# 1-Schematic_sfy1.net
KiCad netlist of a schematic drawn in EasyEDA
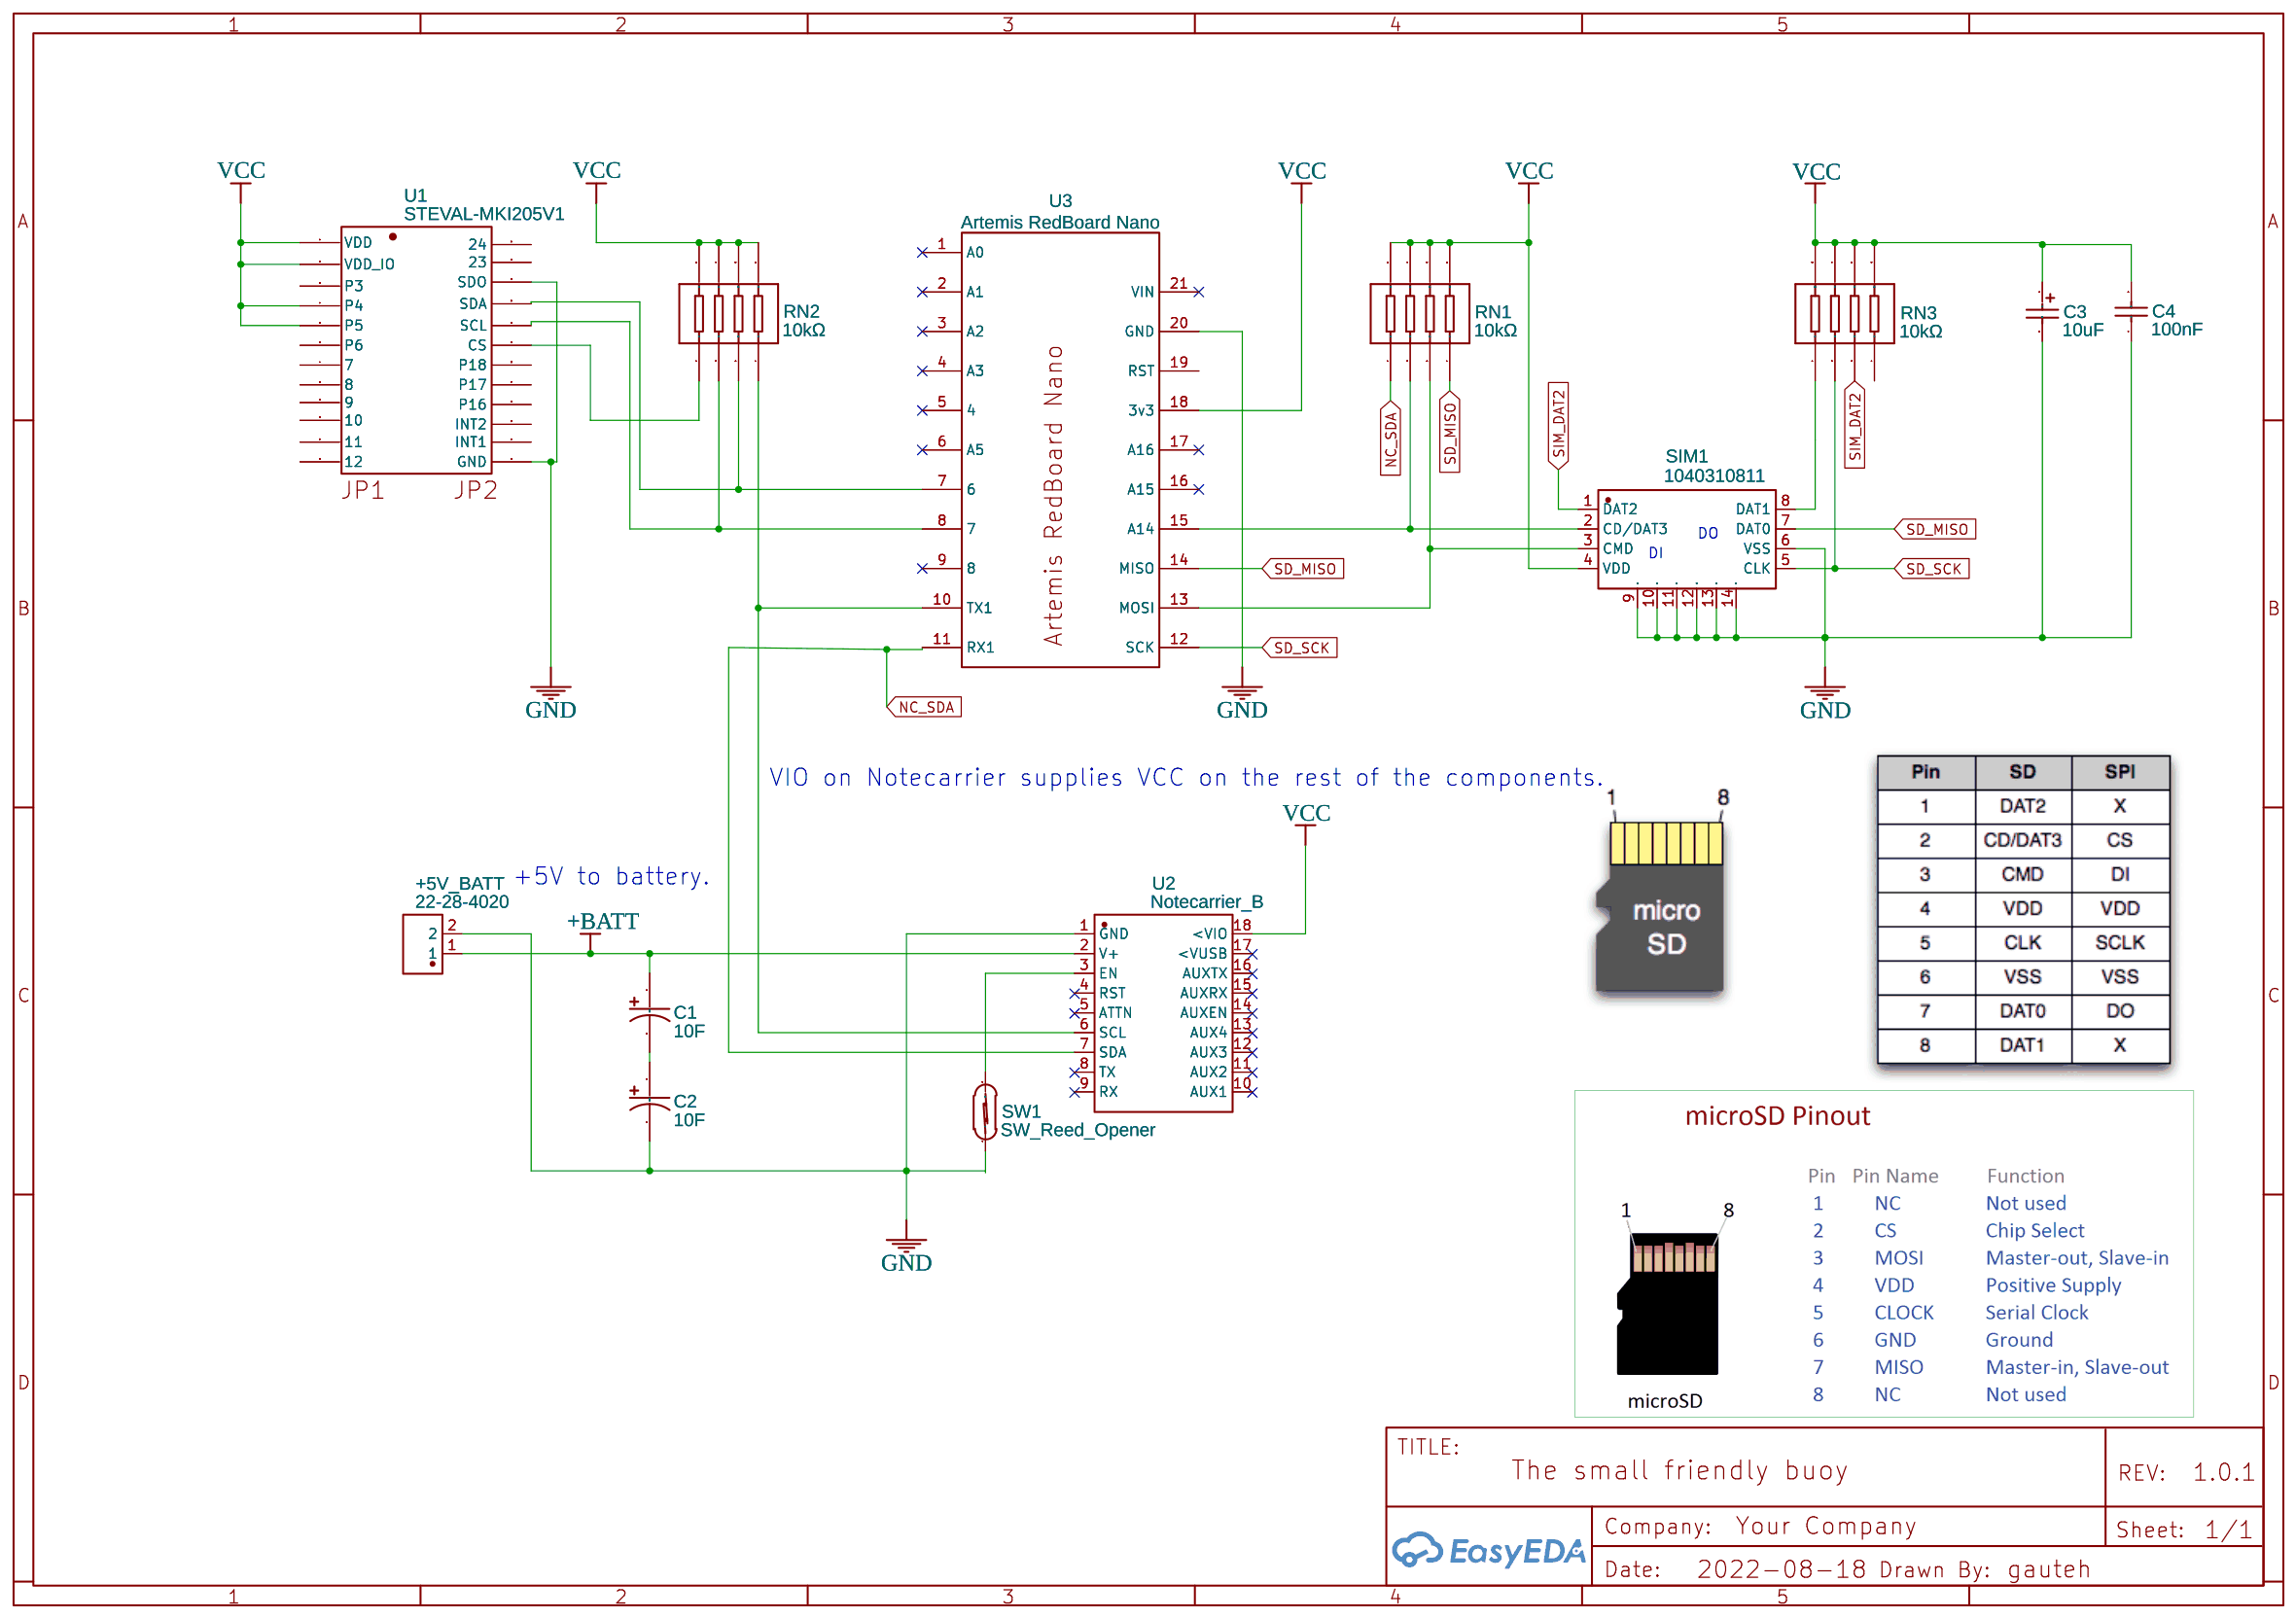
[diagram p0: schematic sheet]

(export (version "E")
  (design (tool "Eeschema 10.0.6"))
  (components
    (comp (ref "+5V_BATT")
      (value "22-28-4020")
      (fields (field (name "BOM_Supplier Part") "C234182"))
      (libsource (lib "") (part "22-28-4020"))
    )
    (comp (ref "C1")
      (value "10F")
      (fields
        (field (name "BOM_Manufacturer Part") "SCCT20B106PRB")
        (field (name "BOM_Supplier Part") "581-SCCT20B106PRB")
      )
      (libsource (lib "") (part "SCCT20B106PRB SuperCapacitor 10F 2.7V"))
    )
    (comp (ref "C2")
      (value "10F")
      (fields
        (field (name "BOM_Manufacturer Part") "SCCT20B106PRB")
        (field (name "BOM_Supplier Part") "581-SCCT20B106PRB")
      )
      (libsource (lib "") (part "SCCT20B106PRB SuperCapacitor 10F 2.7V"))
    )
    (comp (ref "C3")
      (value "10uF")
      (fields
        (field (name "BOM_Manufacturer Part") "TC212A106M010B")
        (field (name "BOM_Supplier Part") "C124849")
      )
      (libsource (lib "") (part "TC212A106M010B"))
    )
    (comp (ref "C4")
      (value "100nF")
      (fields
        (field (name "BOM_Manufacturer Part") "CC0805KRX7R9BB104")
        (field (name "BOM_Supplier Part") "C49678")
      )
      (libsource (lib "") (part "CC0805KRX7R9BB104"))
    )
    (comp (ref "RN1")
      (value "10kΩ")
      (fields
        (field (name "BOM_Manufacturer Part") "4D03WGJ0103T5E")
        (field (name "BOM_Supplier Part") "C29718")
      )
      (libsource (lib "") (part "4D03WGJ0103T5E"))
    )
    (comp (ref "RN2")
      (value "10kΩ")
      (fields
        (field (name "BOM_Manufacturer Part") "4D03WGJ0103T5E")
        (field (name "BOM_Supplier Part") "C29718")
      )
      (libsource (lib "") (part "4D03WGJ0103T5E"))
    )
    (comp (ref "RN3")
      (value "10kΩ")
      (fields
        (field (name "BOM_Manufacturer Part") "4D03WGJ0103T5E")
        (field (name "BOM_Supplier Part") "C29718")
      )
      (libsource (lib "") (part "4D03WGJ0103T5E"))
    )
    (comp (ref "SIM1")
      (value "1040310811")
      (fields (field (name "BOM_Supplier Part") "C585350"))
      (libsource (lib "") (part "1040310811"))
    )
    (comp (ref "SW1") (value "SW_Reed_Opener") (libsource (lib "") (part "SW_Reed_Opener")))
    (comp (ref "U1") (value "STEVAL-MKI205V1") (libsource (lib "") (part "STEVAL-MKI205V1")))
    (comp (ref "U2") (value "Notecarrier_B") (libsource (lib "") (part "Notecarrier_B")))
    (comp (ref "U3") (value "Artemis RedBoard Nano") (libsource (lib "") (part "Artemis RedBoard Nano")))
  )
  (nets
    (net (code "1") (name "+BATT") (class "Default")
      (node (ref "+5V_BATT") (pin "1") (pinfunction "1_1") (pintype "unspecified"))
      (node (ref "C1") (pin "1") (pinfunction "1_1") (pintype "unspecified"))
      (node (ref "U2") (pin "2") (pinfunction "V+_2") (pintype "unspecified"))
    )
    (net (code "2") (name "GND") (class "Default")
      (node (ref "+5V_BATT") (pin "2") (pinfunction "2_2") (pintype "unspecified"))
      (node (ref "C2") (pin "2") (pinfunction "2_2") (pintype "unspecified"))
      (node (ref "C3") (pin "2") (pinfunction "2_2") (pintype "input"))
      (node (ref "C4") (pin "1") (pinfunction "1_1") (pintype "input"))
      (node (ref "SIM1") (pin "10") (pinfunction "10_10") (pintype "unspecified"))
      (node (ref "SIM1") (pin "11") (pinfunction "11_11") (pintype "unspecified"))
      (node (ref "SIM1") (pin "12") (pinfunction "12_12") (pintype "unspecified"))
      (node (ref "SIM1") (pin "13") (pinfunction "13_13") (pintype "unspecified"))
      (node (ref "SIM1") (pin "14") (pinfunction "14_14") (pintype "unspecified"))
      (node (ref "SIM1") (pin "6") (pinfunction "VSS_6") (pintype "unspecified"))
      (node (ref "SIM1") (pin "9") (pinfunction "9_9") (pintype "unspecified"))
      (node (ref "U1") (pin "13") (pinfunction "GND_13") (pintype "passive"))
      (node (ref "U1") (pin "22") (pinfunction "SDO_22") (pintype "unspecified"))
      (node (ref "U2") (pin "1") (pinfunction "GND_1") (pintype "unspecified"))
      (node (ref "U3") (pin "20") (pinfunction "GND_20") (pintype "unspecified"))
    )
    (net (code "3") (name "NC_SDA") (class "Default")
      (node (ref "RN1") (pin "1") (pinfunction "1_1") (pintype "input"))
      (node (ref "U2") (pin "7") (pinfunction "SDA_7") (pintype "unspecified"))
      (node (ref "U3") (pin "11") (pinfunction "RX1_11") (pintype "unspecified"))
    )
    (net (code "4") (name "Net-(C1-Pad2)") (class "Default")
      (node (ref "C1") (pin "2") (pinfunction "2_2") (pintype "unspecified"))
      (node (ref "C2") (pin "1") (pinfunction "1_1") (pintype "unspecified"))
    )
    (net (code "5") (name "Net-(SIM1-CD{slash}DAT3)") (class "Default")
      (node (ref "RN1") (pin "2") (pinfunction "2_2") (pintype "input"))
      (node (ref "SIM1") (pin "2") (pinfunction "CD/DAT3_2") (pintype "unspecified"))
      (node (ref "U3") (pin "15") (pinfunction "A14_15") (pintype "unspecified"))
    )
    (net (code "6") (name "Net-(SIM1-CMD)") (class "Default")
      (node (ref "RN1") (pin "3") (pinfunction "3_3") (pintype "input"))
      (node (ref "SIM1") (pin "3") (pinfunction "CMD_3") (pintype "unspecified"))
      (node (ref "U3") (pin "13") (pinfunction "MOSI_13") (pintype "unspecified"))
    )
    (net (code "7") (name "Net-(SIM1-DAT1)") (class "Default")
      (node (ref "RN3") (pin "1") (pinfunction "1_1") (pintype "input"))
      (node (ref "SIM1") (pin "8") (pinfunction "DAT1_8") (pintype "unspecified"))
    )
    (net (code "8") (name "Net-(U1-CS)") (class "Default")
      (node (ref "RN2") (pin "1") (pinfunction "1_1") (pintype "input"))
      (node (ref "U1") (pin "19") (pinfunction "CS_19") (pintype "unspecified"))
    )
    (net (code "9") (name "Net-(U1-SCL)") (class "Default")
      (node (ref "RN2") (pin "2") (pinfunction "2_2") (pintype "input"))
      (node (ref "U1") (pin "20") (pinfunction "SCL_20") (pintype "unspecified"))
      (node (ref "U3") (pin "8") (pinfunction "7_8") (pintype "unspecified"))
    )
    (net (code "10") (name "Net-(U1-SDA)") (class "Default")
      (node (ref "RN2") (pin "3") (pinfunction "3_3") (pintype "input"))
      (node (ref "U1") (pin "21") (pinfunction "SDA_21") (pintype "unspecified"))
      (node (ref "U3") (pin "7") (pinfunction "6_7") (pintype "unspecified"))
    )
    (net (code "11") (name "Net-(U2-EN)") (class "Default")
      (node (ref "SW1") (pin "2") (pinfunction "2_2") (pintype "input"))
      (node (ref "U2") (pin "3") (pinfunction "EN_3") (pintype "unspecified"))
    )
    (net (code "12") (name "Net-(U2-SCL)") (class "Default")
      (node (ref "RN2") (pin "4") (pinfunction "4_4") (pintype "input"))
      (node (ref "U2") (pin "6") (pinfunction "SCL_6") (pintype "unspecified"))
      (node (ref "U3") (pin "10") (pinfunction "TX1_10") (pintype "unspecified"))
    )
    (net (code "13") (name "SD_MISO") (class "Default")
      (node (ref "RN1") (pin "4") (pinfunction "4_4") (pintype "input"))
      (node (ref "SIM1") (pin "7") (pinfunction "DAT0_7") (pintype "unspecified"))
      (node (ref "U3") (pin "14") (pinfunction "MISO_14") (pintype "unspecified"))
    )
    (net (code "14") (name "SD_SCK") (class "Default")
      (node (ref "RN3") (pin "2") (pinfunction "2_2") (pintype "input"))
      (node (ref "SIM1") (pin "5") (pinfunction "CLK_5") (pintype "unspecified"))
      (node (ref "U3") (pin "12") (pinfunction "SCK_12") (pintype "unspecified"))
    )
    (net (code "15") (name "SIM_DAT2") (class "Default")
      (node (ref "RN3") (pin "3") (pinfunction "3_3") (pintype "input"))
      (node (ref "SIM1") (pin "1") (pinfunction "DAT2_1") (pintype "unspecified"))
    )
    (net (code "16") (name "VCC") (class "Default")
      (node (ref "C3") (pin "1") (pinfunction "1_1") (pintype "input"))
      (node (ref "C4") (pin "2") (pinfunction "2_2") (pintype "input"))
      (node (ref "RN1") (pin "5") (pinfunction "5_5") (pintype "input"))
      (node (ref "RN1") (pin "6") (pinfunction "6_6") (pintype "input"))
      (node (ref "RN1") (pin "7") (pinfunction "7_7") (pintype "input"))
      (node (ref "RN1") (pin "8") (pinfunction "8_8") (pintype "input"))
      (node (ref "RN2") (pin "5") (pinfunction "5_5") (pintype "input"))
      (node (ref "RN2") (pin "6") (pinfunction "6_6") (pintype "input"))
      (node (ref "RN2") (pin "7") (pinfunction "7_7") (pintype "input"))
      (node (ref "RN2") (pin "8") (pinfunction "8_8") (pintype "input"))
      (node (ref "RN3") (pin "5") (pinfunction "5_5") (pintype "input"))
      (node (ref "RN3") (pin "6") (pinfunction "6_6") (pintype "input"))
      (node (ref "RN3") (pin "7") (pinfunction "7_7") (pintype "input"))
      (node (ref "RN3") (pin "8") (pinfunction "8_8") (pintype "input"))
      (node (ref "SIM1") (pin "4") (pinfunction "VDD_4") (pintype "unspecified"))
      (node (ref "U1") (pin "1") (pinfunction "VDD_1") (pintype "passive"))
      (node (ref "U1") (pin "2") (pinfunction "VDD_IO_2") (pintype "passive"))
      (node (ref "U1") (pin "4") (pinfunction "P4_4") (pintype "unspecified"))
      (node (ref "U1") (pin "5") (pinfunction "P5_5") (pintype "unspecified"))
      (node (ref "U2") (pin "18") (pinfunction "<VIO_18") (pintype "unspecified"))
      (node (ref "U3") (pin "18") (pinfunction "3v3_18") (pintype "unspecified"))
    )
    (net (code "17") (name "unconnected-(RN3-Pad4)") (class "Default")
      (node (ref "RN3") (pin "4") (pinfunction "4_4") (pintype "input"))
    )
    (net (code "18") (name "unconnected-(SW1-Pad1)") (class "Default")
      (node (ref "SW1") (pin "1") (pinfunction "1_1") (pintype "input"))
    )
    (net (code "19") (name "unconnected-(U1-INT1-Pad14)") (class "Default")
      (node (ref "U1") (pin "14") (pinfunction "INT1_14") (pintype "unspecified"))
    )
    (net (code "20") (name "unconnected-(U1-INT2-Pad15)") (class "Default")
      (node (ref "U1") (pin "15") (pinfunction "INT2_15") (pintype "unspecified"))
    )
    (net (code "21") (name "unconnected-(U1-P3-Pad3)") (class "Default")
      (node (ref "U1") (pin "3") (pinfunction "P3_3") (pintype "unspecified"))
    )
    (net (code "22") (name "unconnected-(U1-P6-Pad6)") (class "Default")
      (node (ref "U1") (pin "6") (pinfunction "P6_6") (pintype "unspecified"))
    )
    (net (code "23") (name "unconnected-(U1-P16-Pad16)") (class "Default")
      (node (ref "U1") (pin "16") (pinfunction "P16_16") (pintype "unspecified"))
    )
    (net (code "24") (name "unconnected-(U1-P17-Pad17)") (class "Default")
      (node (ref "U1") (pin "17") (pinfunction "P17_17") (pintype "unspecified"))
    )
    (net (code "25") (name "unconnected-(U1-P18-Pad18)") (class "Default")
      (node (ref "U1") (pin "18") (pinfunction "P18_18") (pintype "unspecified"))
    )
    (net (code "26") (name "unconnected-(U1-Pad7)") (class "Default")
      (node (ref "U1") (pin "7") (pinfunction "7_7") (pintype "unspecified"))
    )
    (net (code "27") (name "unconnected-(U1-Pad8)") (class "Default")
      (node (ref "U1") (pin "8") (pinfunction "8_8") (pintype "unspecified"))
    )
    (net (code "28") (name "unconnected-(U1-Pad9)") (class "Default")
      (node (ref "U1") (pin "9") (pinfunction "9_9") (pintype "unspecified"))
    )
    (net (code "29") (name "unconnected-(U1-Pad10)") (class "Default")
      (node (ref "U1") (pin "10") (pinfunction "10_10") (pintype "unspecified"))
    )
    (net (code "30") (name "unconnected-(U1-Pad11)") (class "Default")
      (node (ref "U1") (pin "11") (pinfunction "11_11") (pintype "unspecified"))
    )
    (net (code "31") (name "unconnected-(U1-Pad12)") (class "Default")
      (node (ref "U1") (pin "12") (pinfunction "12_12") (pintype "unspecified"))
    )
    (net (code "32") (name "unconnected-(U1-Pad23)") (class "Default")
      (node (ref "U1") (pin "23") (pinfunction "23_23") (pintype "unspecified"))
    )
    (net (code "33") (name "unconnected-(U1-Pad24)") (class "Default")
      (node (ref "U1") (pin "24") (pinfunction "24_24") (pintype "unspecified"))
    )
    (net (code "34") (name "unconnected-(U2-<VUSB-Pad17)") (class "Default")
      (node (ref "U2") (pin "17") (pinfunction "<VUSB_17") (pintype "unspecified"))
    )
    (net (code "35") (name "unconnected-(U2-ATTN-Pad5)") (class "Default")
      (node (ref "U2") (pin "5") (pinfunction "ATTN_5") (pintype "unspecified"))
    )
    (net (code "36") (name "unconnected-(U2-AUX1-Pad10)") (class "Default")
      (node (ref "U2") (pin "10") (pinfunction "AUX1_10") (pintype "unspecified"))
    )
    (net (code "37") (name "unconnected-(U2-AUX2-Pad11)") (class "Default")
      (node (ref "U2") (pin "11") (pinfunction "AUX2_11") (pintype "unspecified"))
    )
    (net (code "38") (name "unconnected-(U2-AUX3-Pad12)") (class "Default")
      (node (ref "U2") (pin "12") (pinfunction "AUX3_12") (pintype "unspecified"))
    )
    (net (code "39") (name "unconnected-(U2-AUX4-Pad13)") (class "Default")
      (node (ref "U2") (pin "13") (pinfunction "AUX4_13") (pintype "unspecified"))
    )
    (net (code "40") (name "unconnected-(U2-AUXEN-Pad14)") (class "Default")
      (node (ref "U2") (pin "14") (pinfunction "AUXEN_14") (pintype "unspecified"))
    )
    (net (code "41") (name "unconnected-(U2-AUXRX-Pad15)") (class "Default")
      (node (ref "U2") (pin "15") (pinfunction "AUXRX_15") (pintype "unspecified"))
    )
    (net (code "42") (name "unconnected-(U2-AUXTX-Pad16)") (class "Default")
      (node (ref "U2") (pin "16") (pinfunction "AUXTX_16") (pintype "unspecified"))
    )
    (net (code "43") (name "unconnected-(U2-RST-Pad4)") (class "Default")
      (node (ref "U2") (pin "4") (pinfunction "RST_4") (pintype "unspecified"))
    )
    (net (code "44") (name "unconnected-(U2-RX-Pad9)") (class "Default")
      (node (ref "U2") (pin "9") (pinfunction "RX_9") (pintype "unspecified"))
    )
    (net (code "45") (name "unconnected-(U2-TX-Pad8)") (class "Default")
      (node (ref "U2") (pin "8") (pinfunction "TX_8") (pintype "unspecified"))
    )
    (net (code "46") (name "unconnected-(U3-4-Pad5)") (class "Default")
      (node (ref "U3") (pin "5") (pinfunction "4_5") (pintype "unspecified+no_connect"))
    )
    (net (code "47") (name "unconnected-(U3-8-Pad9)") (class "Default")
      (node (ref "U3") (pin "9") (pinfunction "8_9") (pintype "unspecified+no_connect"))
    )
    (net (code "48") (name "unconnected-(U3-A0-Pad1)") (class "Default")
      (node (ref "U3") (pin "1") (pinfunction "A0_1") (pintype "unspecified+no_connect"))
    )
    (net (code "49") (name "unconnected-(U3-A1-Pad2)") (class "Default")
      (node (ref "U3") (pin "2") (pinfunction "A1_2") (pintype "unspecified+no_connect"))
    )
    (net (code "50") (name "unconnected-(U3-A2-Pad3)") (class "Default")
      (node (ref "U3") (pin "3") (pinfunction "A2_3") (pintype "unspecified+no_connect"))
    )
    (net (code "51") (name "unconnected-(U3-A3-Pad4)") (class "Default")
      (node (ref "U3") (pin "4") (pinfunction "A3_4") (pintype "unspecified+no_connect"))
    )
    (net (code "52") (name "unconnected-(U3-A5-Pad6)") (class "Default")
      (node (ref "U3") (pin "6") (pinfunction "A5_6") (pintype "unspecified+no_connect"))
    )
    (net (code "53") (name "unconnected-(U3-A15-Pad16)") (class "Default")
      (node (ref "U3") (pin "16") (pinfunction "A15_16") (pintype "unspecified+no_connect"))
    )
    (net (code "54") (name "unconnected-(U3-A16-Pad17)") (class "Default")
      (node (ref "U3") (pin "17") (pinfunction "A16_17") (pintype "unspecified+no_connect"))
    )
    (net (code "55") (name "unconnected-(U3-RST-Pad19)") (class "Default")
      (node (ref "U3") (pin "19") (pinfunction "RST_19") (pintype "unspecified"))
    )
    (net (code "56") (name "unconnected-(U3-VIN-Pad21)") (class "Default")
      (node (ref "U3") (pin "21") (pinfunction "VIN_21") (pintype "unspecified+no_connect"))
    )
  )
)
